# TMC5160_BOB_V1_2.net
KiCad netlist of a schematic drawn in Altium Designer
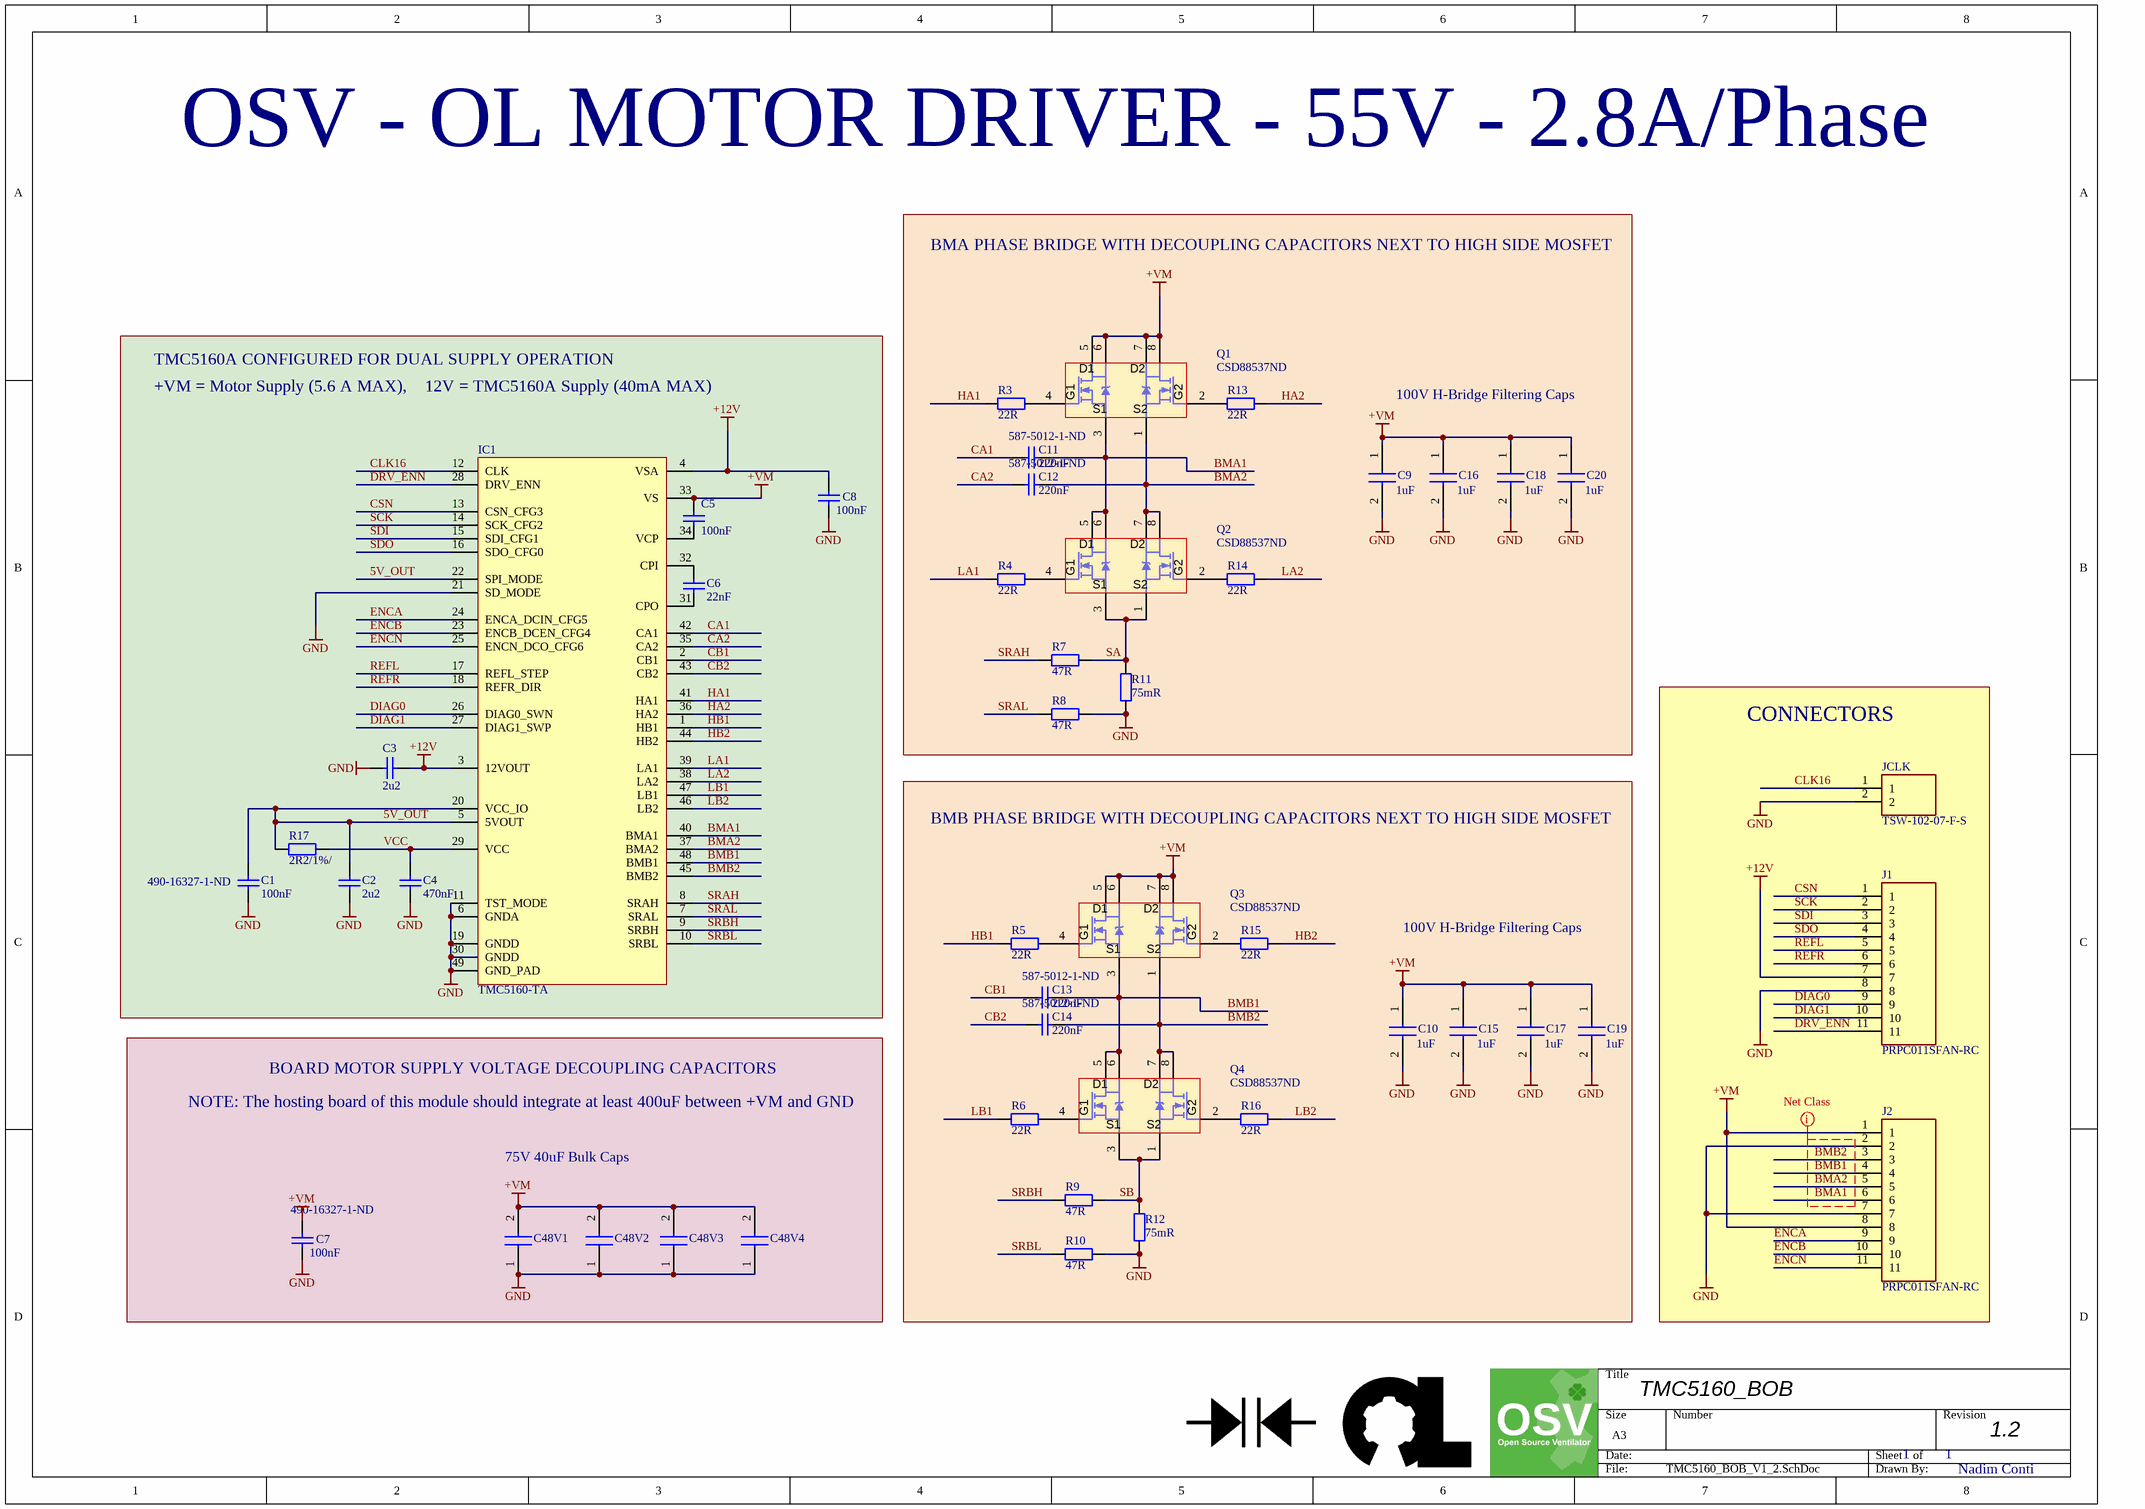
[diagram p0: TMC5160_BOB_V1_2.SchDoc]

(export (version "E")
  (design (tool "Eeschema 10.0.6"))
  (components
    (comp (ref "C1")
      (value "100nF")
      (footprint "C0603")
      (description "Cap Ceramic 0.1uF 100V X7R 20% Pad SMD 0603 125C T/R")
      (fields
        (field (name "SUPPLIER PART NUMBER 1") "490-16327-1-ND")
        (field (name "MANUFACTURER") "Murata")
        (field (name "MANUFACTURER PART NUMBER") "GRM188R72A104MA35D")
      )
      (libsource (lib "SCH Passives") (part "Capacitor"))
    )
    (comp (ref "C2")
      (value "2u2")
      (footprint "C0603")
      (description "SMD Multilayer Ceramic Capacitor, 0603 [1608 Metric], 2.2 µF, 25 V, ± 10%, X5R, GRM Series")
      (fields (field (name "MF") "MURATA") (field (name "MPN") "GRM188R61E225KA12D"))
      (libsource (lib "TMC5160_RevA") (part "2.2 µF, 25 V, ± 10%, X5R, GRM Series"))
    )
    (comp (ref "C3")
      (value "2u2")
      (footprint "C0603")
      (description "SMD Multilayer Ceramic Capacitor, 0603 [1608 Metric], 2.2 µF, 25 V, ± 10%, X5R, GRM Series")
      (fields (field (name "MF") "MURATA") (field (name "MPN") "GRM188R61E225KA12D"))
      (libsource (lib "TMC5160_RevA") (part "2.2 µF, 25 V, ± 10%, X5R, GRM Series"))
    )
    (comp (ref "C4")
      (value "470nF")
      (footprint "C0603")
      (description "Ceramic capacitor")
      (fields (field (name "MF") "Multicomp") (field (name "MPN") "MC0603X474K160CT"))
      (libsource (lib "SCH Passives") (part "Capacitor"))
    )
    (comp (ref "C5")
      (value "100nF")
      (footprint "C0603")
      (description "Cap Ceramic 0.1uF 100V X7R 20% Pad SMD 0603 125C T/R")
      (fields
        (field (name "MANUFACTURER") "Murata")
        (field (name "MANUFACTURER PART NUMBER") "GRM188R72A104MA35D")
      )
      (libsource (lib "SCH Passives") (part "Capacitor"))
    )
    (comp (ref "C6")
      (value "22nF")
      (footprint "C0603")
      (description "Ceramic capacitor")
      (fields (field (name "MF") "Multicomp") (field (name "MPN") "MC0603B223K500CT"))
      (libsource (lib "SCH Passives") (part "Capacitor"))
    )
    (comp (ref "C7")
      (value "100nF")
      (footprint "C0603")
      (description "Cap Ceramic 0.1uF 100V X7R 20% Pad SMD 0603 125C T/R")
      (fields
        (field (name "SUPPLIER PART NUMBER 1") "490-16327-1-ND")
        (field (name "MANUFACTURER") "Murata")
        (field (name "MANUFACTURER PART NUMBER") "GRM188R72A104MA35D")
      )
      (libsource (lib "SCH Passives") (part "Capacitor"))
    )
    (comp (ref "C8")
      (value "100nF")
      (footprint "C0603")
      (description "Cap Ceramic 0.1uF 100V X7R 20% Pad SMD 0603 125C T/R")
      (fields
        (field (name "MANUFACTURER") "Murata")
        (field (name "MANUFACTURER PART NUMBER") "GRM188R72A104MA35D")
      )
      (libsource (lib "SCH Passives") (part "Capacitor"))
    )
    (comp (ref "C9")
      (value "1uF")
      (footprint "SamacSys:CAPC2012X145N")
      (description "Capacitor")
      (fields
        (field (name "MANUFACTURER_PART_NUMBER") "GRM21BC72A105KE01L")
        (field (name "MOUSER PART NUMBER") "81-GRM21BC72A105KE1L")
      )
      (libsource (lib "*") (part "GRM21BC72A105KE01L"))
    )
    (comp (ref "C10")
      (value "1uF")
      (footprint "SamacSys:CAPC2012X145N")
      (description "Capacitor")
      (fields
        (field (name "MANUFACTURER_PART_NUMBER") "GRM21BC72A105KE01L")
        (field (name "MOUSER PART NUMBER") "81-GRM21BC72A105KE1L")
      )
      (libsource (lib "*") (part "GRM21BC72A105KE01L"))
    )
    (comp (ref "C11")
      (value "220nF")
      (footprint "C0402")
      (description "CAP CER 0.22UF 100V X7S 0603")
      (fields
        (field (name "SUPPLIER PART NUMBER 1") "587-5012-1-ND")
        (field (name "MANUFACTURER") "Taiyo Yuden")
        (field (name "MANUFACTURER PART NUMBER") "HMK107C7224KAHTE")
      )
      (libsource (lib "TMC5160_RevA") (part "0.22 µF, 50 V, ± 10%, X7R"))
    )
    (comp (ref "C12")
      (value "220nF")
      (footprint "C0402")
      (description "CAP CER 0.22UF 100V X7S 0603")
      (fields
        (field (name "SUPPLIER PART NUMBER 1") "587-5012-1-ND")
        (field (name "MANUFACTURER") "Taiyo Yuden")
        (field (name "MANUFACTURER PART NUMBER") "HMK107C7224KAHTE")
      )
      (libsource (lib "TMC5160_RevA") (part "0.22 µF, 50 V, ± 10%, X7R"))
    )
    (comp (ref "C13")
      (value "220nF")
      (footprint "C0402")
      (description "CAP CER 0.22UF 100V X7S 0603")
      (fields
        (field (name "SUPPLIER PART NUMBER 1") "587-5012-1-ND")
        (field (name "MANUFACTURER") "Taiyo Yuden")
        (field (name "MANUFACTURER PART NUMBER") "HMK107C7224KAHTE")
      )
      (libsource (lib "TMC5160_RevA") (part "0.22 µF, 50 V, ± 10%, X7R"))
    )
    (comp (ref "C14")
      (value "220nF")
      (footprint "C0402")
      (description "CAP CER 0.22UF 100V X7S 0603")
      (fields
        (field (name "SUPPLIER PART NUMBER 1") "587-5012-1-ND")
        (field (name "MANUFACTURER") "Taiyo Yuden")
        (field (name "MANUFACTURER PART NUMBER") "HMK107C7224KAHTE")
      )
      (libsource (lib "TMC5160_RevA") (part "0.22 µF, 50 V, ± 10%, X7R"))
    )
    (comp (ref "C15")
      (value "1uF")
      (footprint "SamacSys:CAPC2012X145N")
      (description "Capacitor")
      (fields
        (field (name "MANUFACTURER_PART_NUMBER") "GRM21BC72A105KE01L")
        (field (name "MOUSER PART NUMBER") "81-GRM21BC72A105KE1L")
      )
      (libsource (lib "*") (part "GRM21BC72A105KE01L"))
    )
    (comp (ref "C16")
      (value "1uF")
      (footprint "SamacSys:CAPC2012X145N")
      (description "Capacitor")
      (fields
        (field (name "MANUFACTURER_PART_NUMBER") "GRM21BC72A105KE01L")
        (field (name "MOUSER PART NUMBER") "81-GRM21BC72A105KE1L")
      )
      (libsource (lib "*") (part "GRM21BC72A105KE01L"))
    )
    (comp (ref "C17")
      (value "1uF")
      (footprint "SamacSys:CAPC2012X145N")
      (description "Capacitor")
      (fields
        (field (name "MANUFACTURER_PART_NUMBER") "GRM21BC72A105KE01L")
        (field (name "MOUSER PART NUMBER") "81-GRM21BC72A105KE1L")
      )
      (libsource (lib "*") (part "GRM21BC72A105KE01L"))
    )
    (comp (ref "C18")
      (value "1uF")
      (footprint "SamacSys:CAPC2012X145N")
      (description "Capacitor")
      (fields
        (field (name "MANUFACTURER_PART_NUMBER") "GRM21BC72A105KE01L")
        (field (name "MOUSER PART NUMBER") "81-GRM21BC72A105KE1L")
      )
      (libsource (lib "*") (part "GRM21BC72A105KE01L"))
    )
    (comp (ref "C19")
      (value "1uF")
      (footprint "SamacSys:CAPC2012X145N")
      (description "Capacitor")
      (fields
        (field (name "MANUFACTURER_PART_NUMBER") "GRM21BC72A105KE01L")
        (field (name "MOUSER PART NUMBER") "81-GRM21BC72A105KE1L")
      )
      (libsource (lib "*") (part "GRM21BC72A105KE01L"))
    )
    (comp (ref "C20")
      (value "1uF")
      (footprint "SamacSys:CAPC2012X145N")
      (description "Capacitor")
      (fields
        (field (name "MANUFACTURER_PART_NUMBER") "GRM21BC72A105KE01L")
        (field (name "MOUSER PART NUMBER") "81-GRM21BC72A105KE1L")
      )
      (libsource (lib "*") (part "GRM21BC72A105KE01L"))
    )
    (comp (ref "C48V1")
      (value "C3225X7R1N106K250AC")
      (footprint "SamacSys:CAPC3225X230N")
      (description "Capacitor")
      (fields (field (name "MOUSER PART NUMBER") "810-C3225X7R1N106K25"))
      (libsource (lib "*") (part "C3225X7R1N106K250AC"))
    )
    (comp (ref "C48V2")
      (value "C3225X7R1N106K250AC")
      (footprint "SamacSys:CAPC3225X230N")
      (description "Capacitor")
      (fields (field (name "MOUSER PART NUMBER") "810-C3225X7R1N106K25"))
      (libsource (lib "*") (part "C3225X7R1N106K250AC"))
    )
    (comp (ref "C48V3")
      (value "C3225X7R1N106K250AC")
      (footprint "SamacSys:CAPC3225X230N")
      (description "Capacitor")
      (fields (field (name "MOUSER PART NUMBER") "810-C3225X7R1N106K25"))
      (libsource (lib "*") (part "C3225X7R1N106K250AC"))
    )
    (comp (ref "C48V4")
      (value "C3225X7R1N106K250AC")
      (footprint "SamacSys:CAPC3225X230N")
      (description "Capacitor")
      (fields (field (name "MOUSER PART NUMBER") "810-C3225X7R1N106K25"))
      (libsource (lib "*") (part "C3225X7R1N106K250AC"))
    )
    (comp (ref "IC1")
      (value "TMC5160-TA")
      (footprint "TMC5160_TSQFP50P900X900X120_HS-49L")
      (fields (field (name "MANUFACTURER") "TRINAMIC"))
      (libsource (lib "TMC5160_RevA") (part "TMC5160-TA"))
    )
    (comp (ref "J1")
      (value "PRPC011SFAN-RC")
      (footprint "SamacSys:HDRV11W64P254_1X11_2794X254X1058P")
      (description "Connector")
      (libsource (lib "*") (part "PRPC011SFAN-RC"))
    )
    (comp (ref "J2")
      (value "PRPC011SFAN-RC")
      (footprint "SamacSys:HDRV11W64P254_1X11_2794X254X1058P")
      (description "Connector")
      (libsource (lib "*") (part "PRPC011SFAN-RC"))
    )
    (comp (ref "JCLK")
      (value "TSW-102-07-F-S")
      (footprint "SamacSys:HDRV2W64P254_1X2_508X241X838P")
      (description "Connector")
      (fields (field (name "MOUSER PART NUMBER") "200-TSW10207FS") (field (name "RS PART NUMBER") "1557967"))
      (libsource (lib "*") (part "TSW-102-07-F-S"))
    )
    (comp (ref "Q1")
      (value "CSD88537ND")
      (footprint "SOP127P600X170-8L")
      (description "Mosfet Array 2 N-Channel (Dual) 60V 15A 2.1W Surface Mount 8-SOIC")
      (fields (field (name "MF") "Texas Instruments"))
      (libsource (lib "TMC5160_BOB_V1_2") (part "CSD88537ND MOSFET 2N-CH 60V 15A 8SOIC"))
    )
    (comp (ref "Q2")
      (value "CSD88537ND")
      (footprint "SOP127P600X170-8L")
      (description "Mosfet Array 2 N-Channel (Dual) 60V 15A 2.1W Surface Mount 8-SOIC")
      (fields (field (name "MF") "Texas Instruments"))
      (libsource (lib "TMC5160_BOB_V1_2") (part "CSD88537ND MOSFET 2N-CH 60V 15A 8SOIC"))
    )
    (comp (ref "Q3")
      (value "CSD88537ND")
      (footprint "SOP127P600X170-8L")
      (description "Mosfet Array 2 N-Channel (Dual) 60V 15A 2.1W Surface Mount 8-SOIC")
      (fields (field (name "MF") "Texas Instruments"))
      (libsource (lib "TMC5160_BOB_V1_2") (part "CSD88537ND MOSFET 2N-CH 60V 15A 8SOIC"))
    )
    (comp (ref "Q4")
      (value "CSD88537ND")
      (footprint "SOP127P600X170-8L")
      (description "Mosfet Array 2 N-Channel (Dual) 60V 15A 2.1W Surface Mount 8-SOIC")
      (fields (field (name "MF") "Texas Instruments"))
      (libsource (lib "TMC5160_BOB_V1_2") (part "CSD88537ND MOSFET 2N-CH 60V 15A 8SOIC"))
    )
    (comp (ref "R3")
      (value "22R / 100mW / 1%")
      (footprint "R0603")
      (description "SMD Chip Resistor, Thick Film, 22 ohm, 50 V, 0603 [1608 Metric], 100 mW, ± 1%, MCWR Series")
      (fields
        (field (name "MPN") "MCWR06X22R0FTLV")
        (field (name "MF") "MULTICOMP")
        (field (name "RESISTANCE") "22R")
      )
      (libsource (lib "TMC5160_RevA") (part "22 ohm, 50 V, 0603 [1608 Metric], 100 mW, ± 1%, MCWR Series"))
    )
    (comp (ref "R4")
      (value "22R / 100mW / 1%")
      (footprint "R0603")
      (description "SMD Chip Resistor, Thick Film, 22 ohm, 50 V, 0603 [1608 Metric], 100 mW, ± 1%, MCWR Series")
      (fields
        (field (name "MPN") "MCWR06X22R0FTLV")
        (field (name "MF") "MULTICOMP")
        (field (name "RESISTANCE") "22R")
      )
      (libsource (lib "TMC5160_RevA") (part "22 ohm, 50 V, 0603 [1608 Metric], 100 mW, ± 1%, MCWR Series"))
    )
    (comp (ref "R5")
      (value "22R / 100mW / 1%")
      (footprint "R0603")
      (description "SMD Chip Resistor, Thick Film, 22 ohm, 50 V, 0603 [1608 Metric], 100 mW, ± 1%, MCWR Series")
      (fields
        (field (name "MPN") "MCWR06X22R0FTLV")
        (field (name "MF") "MULTICOMP")
        (field (name "RESISTANCE") "22R")
      )
      (libsource (lib "TMC5160_RevA") (part "22 ohm, 50 V, 0603 [1608 Metric], 100 mW, ± 1%, MCWR Series"))
    )
    (comp (ref "R6")
      (value "22R / 100mW / 1%")
      (footprint "R0603")
      (description "SMD Chip Resistor, Thick Film, 22 ohm, 50 V, 0603 [1608 Metric], 100 mW, ± 1%, MCWR Series")
      (fields
        (field (name "MPN") "MCWR06X22R0FTLV")
        (field (name "MF") "MULTICOMP")
        (field (name "RESISTANCE") "22R")
      )
      (libsource (lib "TMC5160_RevA") (part "22 ohm, 50 V, 0603 [1608 Metric], 100 mW, ± 1%, MCWR Series"))
    )
    (comp (ref "R7")
      (value "47R /  / 1%")
      (footprint "R0603")
      (description "SMD Chip Resistor, Ceramic, 47 ohm, 75 V, 0603 [1608 Metric], 100 mW, ± 1%, MCSR 06 Series")
      (fields
        (field (name "MPN") "MCSR06X47R0FTL")
        (field (name "MF") "MULTICOMP")
        (field (name "RESISTANCE") "47R")
      )
      (libsource (lib "TMC5160_RevA") (part "47 ohm, 75 V, 0603 [1608 Metric], 100 mW, ± 1%, MCSR 06 Series"))
    )
    (comp (ref "R8")
      (value "47R /  / 1%")
      (footprint "R0603")
      (description "SMD Chip Resistor, Ceramic, 47 ohm, 75 V, 0603 [1608 Metric], 100 mW, ± 1%, MCSR 06 Series")
      (fields
        (field (name "MPN") "MCSR06X47R0FTL")
        (field (name "MF") "MULTICOMP")
        (field (name "RESISTANCE") "47R")
      )
      (libsource (lib "TMC5160_RevA") (part "47 ohm, 75 V, 0603 [1608 Metric], 100 mW, ± 1%, MCSR 06 Series"))
    )
    (comp (ref "R9")
      (value "47R /  / 1%")
      (footprint "R0603")
      (description "SMD Chip Resistor, Ceramic, 47 ohm, 75 V, 0603 [1608 Metric], 100 mW, ± 1%, MCSR 06 Series")
      (fields
        (field (name "MPN") "MCSR06X47R0FTL")
        (field (name "MF") "MULTICOMP")
        (field (name "RESISTANCE") "47R")
      )
      (libsource (lib "TMC5160_RevA") (part "47 ohm, 75 V, 0603 [1608 Metric], 100 mW, ± 1%, MCSR 06 Series"))
    )
    (comp (ref "R10")
      (value "47R /  / 1%")
      (footprint "R0603")
      (description "SMD Chip Resistor, Ceramic, 47 ohm, 75 V, 0603 [1608 Metric], 100 mW, ± 1%, MCSR 06 Series")
      (fields
        (field (name "MPN") "MCSR06X47R0FTL")
        (field (name "MF") "MULTICOMP")
        (field (name "RESISTANCE") "47R")
      )
      (libsource (lib "TMC5160_RevA") (part "47 ohm, 75 V, 0603 [1608 Metric], 100 mW, ± 1%, MCSR 06 Series"))
    )
    (comp (ref "R11")
      (value "75mR")
      (footprint "R1206")
      (description "SMD Chip Resistor, Thick Film, Current Sense Resistors - SMD 1W 0.075ohm 1%")
      (fields
        (field (name "MPN") "ERJ-8BWFR075V")
        (field (name "MF") "Panasonic Electronic Components")
        (field (name "RESISTANCE") "75mR")
      )
      (libsource (lib "SMD_Passives") (part "R_SENS, 0.075 ohm, 1206, 1W, ± 1%, ERJ Series"))
    )
    (comp (ref "R12")
      (value "75mR")
      (footprint "R1206")
      (description "SMD Chip Resistor, Thick Film, Current Sense Resistors - SMD 1W 0.075ohm 1%")
      (fields
        (field (name "MPN") "ERJ-8BWFR075V")
        (field (name "MF") "Panasonic Electronic Components")
        (field (name "RESISTANCE") "75mR")
      )
      (libsource (lib "SMD_Passives") (part "R_SENS, 0.075 ohm, 1206, 1W, ± 1%, ERJ Series"))
    )
    (comp (ref "R13")
      (value "22R / 100mW / 1%")
      (footprint "R0603")
      (description "SMD Chip Resistor, Thick Film, 22 ohm, 50 V, 0603 [1608 Metric], 100 mW, ± 1%, MCWR Series")
      (fields
        (field (name "MPN") "MCWR06X22R0FTLV")
        (field (name "MF") "MULTICOMP")
        (field (name "RESISTANCE") "22R")
      )
      (libsource (lib "TMC5160_RevA") (part "22 ohm, 50 V, 0603 [1608 Metric], 100 mW, ± 1%, MCWR Series"))
    )
    (comp (ref "R14")
      (value "22R / 100mW / 1%")
      (footprint "R0603")
      (description "SMD Chip Resistor, Thick Film, 22 ohm, 50 V, 0603 [1608 Metric], 100 mW, ± 1%, MCWR Series")
      (fields
        (field (name "MPN") "MCWR06X22R0FTLV")
        (field (name "MF") "MULTICOMP")
        (field (name "RESISTANCE") "22R")
      )
      (libsource (lib "TMC5160_RevA") (part "22 ohm, 50 V, 0603 [1608 Metric], 100 mW, ± 1%, MCWR Series"))
    )
    (comp (ref "R15")
      (value "22R / 100mW / 1%")
      (footprint "R0603")
      (description "SMD Chip Resistor, Thick Film, 22 ohm, 50 V, 0603 [1608 Metric], 100 mW, ± 1%, MCWR Series")
      (fields
        (field (name "MPN") "MCWR06X22R0FTLV")
        (field (name "MF") "MULTICOMP")
        (field (name "RESISTANCE") "22R")
      )
      (libsource (lib "TMC5160_RevA") (part "22 ohm, 50 V, 0603 [1608 Metric], 100 mW, ± 1%, MCWR Series"))
    )
    (comp (ref "R16")
      (value "22R / 100mW / 1%")
      (footprint "R0603")
      (description "SMD Chip Resistor, Thick Film, 22 ohm, 50 V, 0603 [1608 Metric], 100 mW, ± 1%, MCWR Series")
      (fields
        (field (name "MPN") "MCWR06X22R0FTLV")
        (field (name "MF") "MULTICOMP")
        (field (name "RESISTANCE") "22R")
      )
      (libsource (lib "TMC5160_RevA") (part "22 ohm, 50 V, 0603 [1608 Metric], 100 mW, ± 1%, MCWR Series"))
    )
    (comp (ref "R17")
      (value "2R2/1%/")
      (footprint "R0603")
      (description "Resistor")
      (fields (field (name "MPN") "MC0063W060312R2") (field (name "MF") "Multicomp"))
      (libsource (lib "SCH Passives") (part "Resistor"))
    )
  )
  (nets
    (net (code "1") (name "+12V") (class "Default")
      (node (ref "C3") (pin "2") (pinfunction "2_2") (pintype "passive"))
      (node (ref "C8") (pin "1") (pinfunction "1_1") (pintype "passive"))
      (node (ref "IC1") (pin "3") (pinfunction "12VOUT_3") (pintype "passive"))
      (node (ref "IC1") (pin "4") (pinfunction "VSA_4") (pintype "passive"))
      (node (ref "J1") (pin "7") (pinfunction "7_7") (pintype "passive"))
    )
    (net (code "2") (name "+VM") (class "Default")
      (node (ref "C10") (pin "1") (pinfunction "1_1") (pintype "passive"))
      (node (ref "C15") (pin "1") (pinfunction "1_1") (pintype "passive"))
      (node (ref "C16") (pin "1") (pinfunction "1_1") (pintype "passive"))
      (node (ref "C17") (pin "1") (pinfunction "1_1") (pintype "passive"))
      (node (ref "C18") (pin "1") (pinfunction "1_1") (pintype "passive"))
      (node (ref "C19") (pin "1") (pinfunction "1_1") (pintype "passive"))
      (node (ref "C20") (pin "1") (pinfunction "1_1") (pintype "passive"))
      (node (ref "C48V1") (pin "2") (pinfunction "2_2") (pintype "passive"))
      (node (ref "C48V2") (pin "2") (pinfunction "2_2") (pintype "passive"))
      (node (ref "C48V3") (pin "2") (pinfunction "2_2") (pintype "passive"))
      (node (ref "C48V4") (pin "2") (pinfunction "2_2") (pintype "passive"))
      (node (ref "C5") (pin "1") (pinfunction "1_1") (pintype "passive"))
      (node (ref "C7") (pin "1") (pinfunction "1_1") (pintype "passive"))
      (node (ref "C9") (pin "1") (pinfunction "1_1") (pintype "passive"))
      (node (ref "IC1") (pin "33") (pinfunction "VS_33") (pintype "passive"))
      (node (ref "J2") (pin "1") (pinfunction "1_1") (pintype "passive"))
      (node (ref "J2") (pin "8") (pinfunction "8_8") (pintype "passive"))
      (node (ref "Q1") (pin "5") (pinfunction "D1_5") (pintype "passive"))
      (node (ref "Q1") (pin "6") (pinfunction "D1_6") (pintype "passive"))
      (node (ref "Q1") (pin "7") (pinfunction "D2_7") (pintype "passive"))
      (node (ref "Q1") (pin "8") (pinfunction "D2_8") (pintype "passive"))
      (node (ref "Q3") (pin "5") (pinfunction "D1_5") (pintype "passive"))
      (node (ref "Q3") (pin "6") (pinfunction "D1_6") (pintype "passive"))
      (node (ref "Q3") (pin "7") (pinfunction "D2_7") (pintype "passive"))
      (node (ref "Q3") (pin "8") (pinfunction "D2_8") (pintype "passive"))
    )
    (net (code "3") (name "/5V_OUT") (class "Default")
      (node (ref "C1") (pin "1") (pinfunction "1_1") (pintype "passive"))
      (node (ref "C2") (pin "1") (pinfunction "1_1") (pintype "passive"))
      (node (ref "IC1") (pin "20") (pinfunction "VCC_IO_20") (pintype "passive"))
      (node (ref "IC1") (pin "22") (pinfunction "SPI_MODE_22") (pintype "passive"))
      (node (ref "IC1") (pin "5") (pinfunction "5VOUT_5") (pintype "passive"))
      (node (ref "R17") (pin "1") (pinfunction "1_1") (pintype "passive"))
    )
    (net (code "4") (name "/BMA1") (class "Default")
      (node (ref "C11") (pin "2") (pinfunction "2_2") (pintype "passive"))
      (node (ref "IC1") (pin "40") (pinfunction "BMA1_40") (pintype "passive"))
      (node (ref "J2") (pin "6") (pinfunction "6_6") (pintype "passive"))
      (node (ref "Q1") (pin "3") (pinfunction "S1_3") (pintype "passive"))
      (node (ref "Q2") (pin "5") (pinfunction "D1_5") (pintype "passive"))
      (node (ref "Q2") (pin "6") (pinfunction "D1_6") (pintype "passive"))
    )
    (net (code "5") (name "/BMA2") (class "Default")
      (node (ref "C12") (pin "2") (pinfunction "2_2") (pintype "passive"))
      (node (ref "IC1") (pin "37") (pinfunction "BMA2_37") (pintype "passive"))
      (node (ref "J2") (pin "5") (pinfunction "5_5") (pintype "passive"))
      (node (ref "Q1") (pin "1") (pinfunction "S2_1") (pintype "passive"))
      (node (ref "Q2") (pin "7") (pinfunction "D2_7") (pintype "passive"))
      (node (ref "Q2") (pin "8") (pinfunction "D2_8") (pintype "passive"))
    )
    (net (code "6") (name "/BMB1") (class "Default")
      (node (ref "C13") (pin "2") (pinfunction "2_2") (pintype "passive"))
      (node (ref "IC1") (pin "48") (pinfunction "BMB1_48") (pintype "passive"))
      (node (ref "J2") (pin "4") (pinfunction "4_4") (pintype "passive"))
      (node (ref "Q3") (pin "3") (pinfunction "S1_3") (pintype "passive"))
      (node (ref "Q4") (pin "5") (pinfunction "D1_5") (pintype "passive"))
      (node (ref "Q4") (pin "6") (pinfunction "D1_6") (pintype "passive"))
    )
    (net (code "7") (name "/BMB2") (class "Default")
      (node (ref "C14") (pin "2") (pinfunction "2_2") (pintype "passive"))
      (node (ref "IC1") (pin "45") (pinfunction "BMB2_45") (pintype "passive"))
      (node (ref "J2") (pin "3") (pinfunction "3_3") (pintype "passive"))
      (node (ref "Q3") (pin "1") (pinfunction "S2_1") (pintype "passive"))
      (node (ref "Q4") (pin "7") (pinfunction "D2_7") (pintype "passive"))
      (node (ref "Q4") (pin "8") (pinfunction "D2_8") (pintype "passive"))
    )
    (net (code "8") (name "/CA1") (class "Default")
      (node (ref "C11") (pin "1") (pinfunction "1_1") (pintype "passive"))
      (node (ref "IC1") (pin "42") (pinfunction "CA1_42") (pintype "passive"))
    )
    (net (code "9") (name "/CA2") (class "Default")
      (node (ref "C12") (pin "1") (pinfunction "1_1") (pintype "passive"))
      (node (ref "IC1") (pin "35") (pinfunction "CA2_35") (pintype "passive"))
    )
    (net (code "10") (name "/CB1") (class "Default")
      (node (ref "C13") (pin "1") (pinfunction "1_1") (pintype "passive"))
      (node (ref "IC1") (pin "2") (pinfunction "CB1_2") (pintype "passive"))
    )
    (net (code "11") (name "/CB2") (class "Default")
      (node (ref "C14") (pin "1") (pinfunction "1_1") (pintype "passive"))
      (node (ref "IC1") (pin "43") (pinfunction "CB2_43") (pintype "passive"))
    )
    (net (code "12") (name "/CLK16") (class "Default")
      (node (ref "IC1") (pin "12") (pinfunction "CLK_12") (pintype "passive"))
      (node (ref "JCLK") (pin "1") (pinfunction "1_1") (pintype "passive"))
    )
    (net (code "13") (name "/CSN") (class "Default")
      (node (ref "IC1") (pin "13") (pinfunction "CSN_CFG3_13") (pintype "passive"))
      (node (ref "J1") (pin "1") (pinfunction "1_1") (pintype "passive"))
    )
    (net (code "14") (name "/DIAG0") (class "Default")
      (node (ref "IC1") (pin "26") (pinfunction "DIAG0_SWN_26") (pintype "passive"))
      (node (ref "J1") (pin "9") (pinfunction "9_9") (pintype "passive"))
    )
    (net (code "15") (name "/DIAG1") (class "Default")
      (node (ref "IC1") (pin "27") (pinfunction "DIAG1_SWP_27") (pintype "passive"))
      (node (ref "J1") (pin "10") (pinfunction "10_10") (pintype "passive"))
    )
    (net (code "16") (name "/DRV_ENN") (class "Default")
      (node (ref "IC1") (pin "28") (pinfunction "DRV_ENN_28") (pintype "passive"))
      (node (ref "J1") (pin "11") (pinfunction "11_11") (pintype "passive"))
    )
    (net (code "17") (name "/ENCA") (class "Default")
      (node (ref "IC1") (pin "24") (pinfunction "ENCA_DCIN_CFG5_24") (pintype "passive"))
      (node (ref "J2") (pin "9") (pinfunction "9_9") (pintype "passive"))
    )
    (net (code "18") (name "/ENCB") (class "Default")
      (node (ref "IC1") (pin "23") (pinfunction "ENCB_DCEN_CFG4_23") (pintype "passive"))
      (node (ref "J2") (pin "10") (pinfunction "10_10") (pintype "passive"))
    )
    (net (code "19") (name "/ENCN") (class "Default")
      (node (ref "IC1") (pin "25") (pinfunction "ENCN_DCO_CFG6_25") (pintype "passive"))
      (node (ref "J2") (pin "11") (pinfunction "11_11") (pintype "passive"))
    )
    (net (code "20") (name "/HA1") (class "Default")
      (node (ref "IC1") (pin "41") (pinfunction "HA1_41") (pintype "passive"))
      (node (ref "R3") (pin "2") (pinfunction "2_2") (pintype "passive"))
    )
    (net (code "21") (name "/HA2") (class "Default")
      (node (ref "IC1") (pin "36") (pinfunction "HA2_36") (pintype "passive"))
      (node (ref "R13") (pin "1") (pinfunction "1_1") (pintype "passive"))
    )
    (net (code "22") (name "/HB1") (class "Default")
      (node (ref "IC1") (pin "1") (pinfunction "HB1_1") (pintype "passive"))
      (node (ref "R5") (pin "2") (pinfunction "2_2") (pintype "passive"))
    )
    (net (code "23") (name "/HB2") (class "Default")
      (node (ref "IC1") (pin "44") (pinfunction "HB2_44") (pintype "passive"))
      (node (ref "R15") (pin "1") (pinfunction "1_1") (pintype "passive"))
    )
    (net (code "24") (name "/LA1") (class "Default")
      (node (ref "IC1") (pin "39") (pinfunction "LA1_39") (pintype "passive"))
      (node (ref "R4") (pin "2") (pinfunction "2_2") (pintype "passive"))
    )
    (net (code "25") (name "/LA2") (class "Default")
      (node (ref "IC1") (pin "38") (pinfunction "LA2_38") (pintype "passive"))
      (node (ref "R14") (pin "1") (pinfunction "1_1") (pintype "passive"))
    )
    (net (code "26") (name "/LB1") (class "Default")
      (node (ref "IC1") (pin "47") (pinfunction "LB1_47") (pintype "passive"))
      (node (ref "R6") (pin "2") (pinfunction "2_2") (pintype "passive"))
    )
    (net (code "27") (name "/LB2") (class "Default")
      (node (ref "IC1") (pin "46") (pinfunction "LB2_46") (pintype "passive"))
      (node (ref "R16") (pin "1") (pinfunction "1_1") (pintype "passive"))
    )
    (net (code "28") (name "/REFL") (class "Default")
      (node (ref "IC1") (pin "17") (pinfunction "REFL_STEP_17") (pintype "passive"))
      (node (ref "J1") (pin "5") (pinfunction "5_5") (pintype "passive"))
    )
    (net (code "29") (name "/REFR") (class "Default")
      (node (ref "IC1") (pin "18") (pinfunction "REFR_DIR_18") (pintype "passive"))
      (node (ref "J1") (pin "6") (pinfunction "6_6") (pintype "passive"))
    )
    (net (code "30") (name "/SA") (class "Default")
      (node (ref "Q2") (pin "1") (pinfunction "S2_1") (pintype "passive"))
      (node (ref "Q2") (pin "3") (pinfunction "S1_3") (pintype "passive"))
      (node (ref "R11") (pin "1") (pinfunction "1_1") (pintype "passive"))
      (node (ref "R7") (pin "1") (pinfunction "1_1") (pintype "passive"))
    )
    (net (code "31") (name "/SB") (class "Default")
      (node (ref "Q4") (pin "1") (pinfunction "S2_1") (pintype "passive"))
      (node (ref "Q4") (pin "3") (pinfunction "S1_3") (pintype "passive"))
      (node (ref "R12") (pin "1") (pinfunction "1_1") (pintype "passive"))
      (node (ref "R9") (pin "1") (pinfunction "1_1") (pintype "passive"))
    )
    (net (code "32") (name "/SCK") (class "Default")
      (node (ref "IC1") (pin "14") (pinfunction "SCK_CFG2_14") (pintype "passive"))
      (node (ref "J1") (pin "2") (pinfunction "2_2") (pintype "passive"))
    )
    (net (code "33") (name "/SDI") (class "Default")
      (node (ref "IC1") (pin "15") (pinfunction "SDI_CFG1_15") (pintype "passive"))
      (node (ref "J1") (pin "3") (pinfunction "3_3") (pintype "passive"))
    )
    (net (code "34") (name "/SDO") (class "Default")
      (node (ref "IC1") (pin "16") (pinfunction "SDO_CFG0_16") (pintype "passive"))
      (node (ref "J1") (pin "4") (pinfunction "4_4") (pintype "passive"))
    )
    (net (code "35") (name "/SRAH") (class "Default")
      (node (ref "IC1") (pin "8") (pinfunction "SRAH_8") (pintype "passive"))
      (node (ref "R7") (pin "2") (pinfunction "2_2") (pintype "passive"))
    )
    (net (code "36") (name "/SRAL") (class "Default")
      (node (ref "IC1") (pin "7") (pinfunction "SRAL_7") (pintype "passive"))
      (node (ref "R8") (pin "2") (pinfunction "2_2") (pintype "passive"))
    )
    (net (code "37") (name "/SRBH") (class "Default")
      (node (ref "IC1") (pin "9") (pinfunction "SRBH_9") (pintype "passive"))
      (node (ref "R9") (pin "2") (pinfunction "2_2") (pintype "passive"))
    )
    (net (code "38") (name "/SRBL") (class "Default")
      (node (ref "IC1") (pin "10") (pinfunction "SRBL_10") (pintype "passive"))
      (node (ref "R10") (pin "2") (pinfunction "2_2") (pintype "passive"))
    )
    (net (code "39") (name "/VCC") (class "Default")
      (node (ref "C4") (pin "1") (pinfunction "1_1") (pintype "passive"))
      (node (ref "IC1") (pin "29") (pinfunction "VCC_29") (pintype "passive"))
      (node (ref "R17") (pin "2") (pinfunction "2_2") (pintype "passive"))
    )
    (net (code "40") (name "GND") (class "Default")
      (node (ref "C1") (pin "2") (pinfunction "2_2") (pintype "passive"))
      (node (ref "C10") (pin "2") (pinfunction "2_2") (pintype "passive"))
      (node (ref "C15") (pin "2") (pinfunction "2_2") (pintype "passive"))
      (node (ref "C16") (pin "2") (pinfunction "2_2") (pintype "passive"))
      (node (ref "C17") (pin "2") (pinfunction "2_2") (pintype "passive"))
      (node (ref "C18") (pin "2") (pinfunction "2_2") (pintype "passive"))
      (node (ref "C19") (pin "2") (pinfunction "2_2") (pintype "passive"))
      (node (ref "C2") (pin "2") (pinfunction "2_2") (pintype "passive"))
      (node (ref "C20") (pin "2") (pinfunction "2_2") (pintype "passive"))
      (node (ref "C3") (pin "1") (pinfunction "1_1") (pintype "passive"))
      (node (ref "C4") (pin "2") (pinfunction "2_2") (pintype "passive"))
      (node (ref "C48V1") (pin "1") (pinfunction "1_1") (pintype "passive"))
      (node (ref "C48V2") (pin "1") (pinfunction "1_1") (pintype "passive"))
      (node (ref "C48V3") (pin "1") (pinfunction "1_1") (pintype "passive"))
      (node (ref "C48V4") (pin "1") (pinfunction "1_1") (pintype "passive"))
      (node (ref "C7") (pin "2") (pinfunction "2_2") (pintype "passive"))
      (node (ref "C8") (pin "2") (pinfunction "2_2") (pintype "passive"))
      (node (ref "C9") (pin "2") (pinfunction "2_2") (pintype "passive"))
      (node (ref "IC1") (pin "11") (pinfunction "TST_MODE_11") (pintype "passive"))
      (node (ref "IC1") (pin "19") (pinfunction "GNDD_19") (pintype "passive"))
      (node (ref "IC1") (pin "21") (pinfunction "SD_MODE_21") (pintype "passive"))
      (node (ref "IC1") (pin "30") (pinfunction "GNDD_30") (pintype "passive"))
      (node (ref "IC1") (pin "49") (pinfunction "GND_PAD_49") (pintype "passive"))
      (node (ref "IC1") (pin "6") (pinfunction "GNDA_6") (pintype "passive"))
      (node (ref "J1") (pin "8") (pinfunction "8_8") (pintype "passive"))
      (node (ref "J2") (pin "2") (pinfunction "2_2") (pintype "passive"))
      (node (ref "J2") (pin "7") (pinfunction "7_7") (pintype "passive"))
      (node (ref "JCLK") (pin "2") (pinfunction "2_2") (pintype "passive"))
      (node (ref "R10") (pin "1") (pinfunction "1_1") (pintype "passive"))
      (node (ref "R11") (pin "2") (pinfunction "2_2") (pintype "passive"))
      (node (ref "R12") (pin "2") (pinfunction "2_2") (pintype "passive"))
      (node (ref "R8") (pin "1") (pinfunction "1_1") (pintype "passive"))
    )
    (net (code "41") (name "Net-(IC1-CPI)") (class "Default")
      (node (ref "C6") (pin "2") (pinfunction "2_2") (pintype "passive"))
      (node (ref "IC1") (pin "32") (pinfunction "CPI_32") (pintype "passive"))
    )
    (net (code "42") (name "Net-(IC1-CPO)") (class "Default")
      (node (ref "C6") (pin "1") (pinfunction "1_1") (pintype "passive"))
      (node (ref "IC1") (pin "31") (pinfunction "CPO_31") (pintype "passive"))
    )
    (net (code "43") (name "Net-(IC1-VCP)") (class "Default")
      (node (ref "C5") (pin "2") (pinfunction "2_2") (pintype "passive"))
      (node (ref "IC1") (pin "34") (pinfunction "VCP_34") (pintype "passive"))
    )
    (net (code "44") (name "Net-(Q1-G1)") (class "Default")
      (node (ref "Q1") (pin "4") (pinfunction "G1_4") (pintype "passive"))
      (node (ref "R3") (pin "1") (pinfunction "1_1") (pintype "passive"))
    )
    (net (code "45") (name "Net-(Q1-G2)") (class "Default")
      (node (ref "Q1") (pin "2") (pinfunction "G2_2") (pintype "passive"))
      (node (ref "R13") (pin "2") (pinfunction "2_2") (pintype "passive"))
    )
    (net (code "46") (name "Net-(Q2-G1)") (class "Default")
      (node (ref "Q2") (pin "4") (pinfunction "G1_4") (pintype "passive"))
      (node (ref "R4") (pin "1") (pinfunction "1_1") (pintype "passive"))
    )
    (net (code "47") (name "Net-(Q2-G2)") (class "Default")
      (node (ref "Q2") (pin "2") (pinfunction "G2_2") (pintype "passive"))
      (node (ref "R14") (pin "2") (pinfunction "2_2") (pintype "passive"))
    )
    (net (code "48") (name "Net-(Q3-G1)") (class "Default")
      (node (ref "Q3") (pin "4") (pinfunction "G1_4") (pintype "passive"))
      (node (ref "R5") (pin "1") (pinfunction "1_1") (pintype "passive"))
    )
    (net (code "49") (name "Net-(Q3-G2)") (class "Default")
      (node (ref "Q3") (pin "2") (pinfunction "G2_2") (pintype "passive"))
      (node (ref "R15") (pin "2") (pinfunction "2_2") (pintype "passive"))
    )
    (net (code "50") (name "Net-(Q4-G1)") (class "Default")
      (node (ref "Q4") (pin "4") (pinfunction "G1_4") (pintype "passive"))
      (node (ref "R6") (pin "1") (pinfunction "1_1") (pintype "passive"))
    )
    (net (code "51") (name "Net-(Q4-G2)") (class "Default")
      (node (ref "Q4") (pin "2") (pinfunction "G2_2") (pintype "passive"))
      (node (ref "R16") (pin "2") (pinfunction "2_2") (pintype "passive"))
    )
  )
)
